# driver.net
KiCad netlist of a schematic drawn in EAGLE
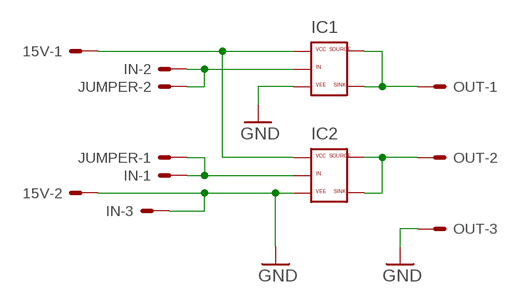
[diagram p0: schematic, sheet 1]

(export (version "E")
  (design (tool "Eeschema 10.0.6"))
  (components
    (comp (ref "15V")
      (value "22-23-2021")
      (footprint "eagle-import:22-23-2021")
      (fields (field (name "MF") "MOLEX"))
      (libsource (lib "eagle-import") (part "22-23-2021"))
    )
    (comp (ref "IC1")
      (value "ZXGD3006E6")
      (footprint "eagle-import:SOT23")
      (libsource (lib "eagle-import") (part "ZXGD3006E6"))
    )
    (comp (ref "IC2")
      (value "ZXGD3006E6")
      (footprint "eagle-import:SOT23")
      (libsource (lib "eagle-import") (part "ZXGD3006E6"))
    )
    (comp (ref "IN")
      (value "22-23-2031")
      (footprint "eagle-import:22-23-2031")
      (fields (field (name "MF") "MOLEX"))
      (libsource (lib "eagle-import") (part "22-23-2031"))
    )
    (comp (ref "JUMPER")
      (value "22-23-2021")
      (footprint "eagle-import:22-23-2021")
      (fields (field (name "MF") "MOLEX"))
      (libsource (lib "eagle-import") (part "22-23-2021"))
    )
    (comp (ref "OUT")
      (value "22-23-2031")
      (footprint "eagle-import:22-23-2031")
      (fields (field (name "MF") "MOLEX"))
      (libsource (lib "eagle-import") (part "22-23-2031"))
    )
  )
  (nets
    (net (code "1") (name "GND") (class "Default")
      (node (ref "15V") (pin "2") (pinfunction "S_2") (pintype "passive"))
      (node (ref "IC1") (pin "3") (pinfunction "VEE_3") (pintype "bidirectional"))
      (node (ref "IC2") (pin "3") (pinfunction "VEE_3") (pintype "bidirectional"))
      (node (ref "IN") (pin "3") (pinfunction "S_3") (pintype "passive"))
      (node (ref "OUT") (pin "3") (pinfunction "S_3") (pintype "passive"))
    )
    (net (code "2") (name "Net-(15VA-S)") (class "Default")
      (node (ref "15V") (pin "1") (pinfunction "S_1") (pintype "passive"))
      (node (ref "IC1") (pin "1") (pinfunction "VCC_1") (pintype "bidirectional"))
      (node (ref "IC2") (pin "1") (pinfunction "VCC_1") (pintype "bidirectional"))
    )
    (net (code "3") (name "Net-(IC1-IN)") (class "Default")
      (node (ref "IC1") (pin "2") (pinfunction "IN_2") (pintype "bidirectional"))
      (node (ref "IN") (pin "2") (pinfunction "S_2") (pintype "passive"))
      (node (ref "JUMPER") (pin "2") (pinfunction "S_2") (pintype "passive"))
    )
    (net (code "4") (name "Net-(IC1-SINK)") (class "Default")
      (node (ref "IC1") (pin "4") (pinfunction "SINK_4") (pintype "bidirectional"))
      (node (ref "IC1") (pin "6") (pinfunction "SOURCE_6") (pintype "bidirectional"))
      (node (ref "OUT") (pin "1") (pinfunction "S_1") (pintype "passive"))
    )
    (net (code "5") (name "Net-(IC2-IN)") (class "Default")
      (node (ref "IC2") (pin "2") (pinfunction "IN_2") (pintype "bidirectional"))
      (node (ref "IN") (pin "1") (pinfunction "S_1") (pintype "passive"))
      (node (ref "JUMPER") (pin "1") (pinfunction "S_1") (pintype "passive"))
    )
    (net (code "6") (name "Net-(IC2-SINK)") (class "Default")
      (node (ref "IC2") (pin "4") (pinfunction "SINK_4") (pintype "bidirectional"))
      (node (ref "IC2") (pin "6") (pinfunction "SOURCE_6") (pintype "bidirectional"))
      (node (ref "OUT") (pin "2") (pinfunction "S_2") (pintype "passive"))
    )
  )
)
